# passlight.net
KiCad netlist of a schematic drawn in EAGLE
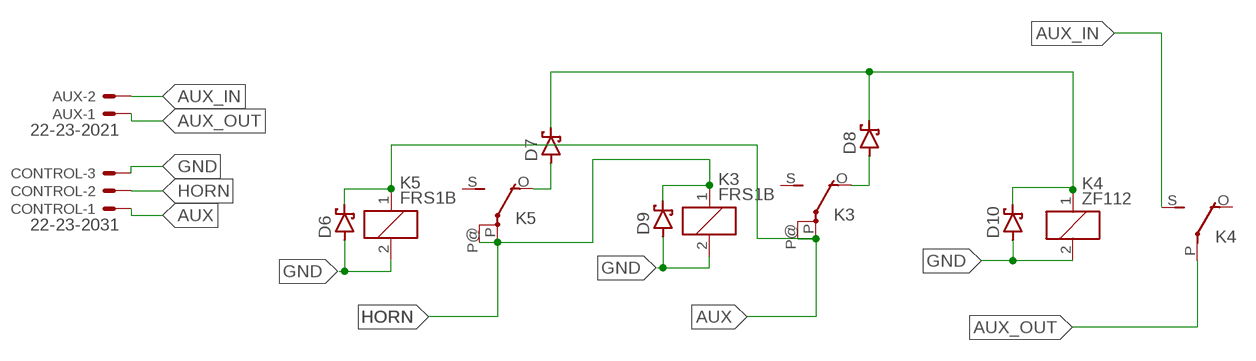
[diagram p0: schematic, sheet 1]

(export (version "E")
  (design (tool "Eeschema 10.0.6"))
  (components
    (comp (ref "AUX")
      (value "22-23-2021")
      (footprint "eagle-import:22-23-2021")
      (fields (field (name "MF") "MOLEX"))
      (libsource (lib "eagle-import") (part "22-23-2021"))
    )
    (comp (ref "CONTROL")
      (value "22-23-2031")
      (footprint "eagle-import:22-23-2031")
      (fields (field (name "MF") "MOLEX"))
      (libsource (lib "eagle-import") (part "22-23-2031"))
    )
    (comp (ref "D6")
      (value "SCHOTTKY-DIODESMD")
      (footprint "eagle-import:SMB")
      (libsource (lib "eagle-import") (part "SCHOTTKY-DIODESMD"))
    )
    (comp (ref "D7")
      (value "SCHOTTKY-DIODESMD")
      (footprint "eagle-import:SMB")
      (libsource (lib "eagle-import") (part "SCHOTTKY-DIODESMD"))
    )
    (comp (ref "D8")
      (value "SCHOTTKY-DIODESMD")
      (footprint "eagle-import:SMB")
      (libsource (lib "eagle-import") (part "SCHOTTKY-DIODESMD"))
    )
    (comp (ref "D9")
      (value "SCHOTTKY-DIODESMD")
      (footprint "eagle-import:SMB")
      (libsource (lib "eagle-import") (part "SCHOTTKY-DIODESMD"))
    )
    (comp (ref "D10")
      (value "SCHOTTKY-DIODESMD")
      (footprint "eagle-import:SMB")
      (libsource (lib "eagle-import") (part "SCHOTTKY-DIODESMD"))
    )
    (comp (ref "K3")
      (value "FRS1B")
      (footprint "eagle-import:FRS1B")
      (libsource (lib "eagle-import") (part "FRS1B"))
    )
    (comp (ref "K4")
      (value "ZF112")
      (footprint "eagle-import:ZF112")
      (libsource (lib "eagle-import") (part "ZF112"))
    )
    (comp (ref "K5")
      (value "FRS1B")
      (footprint "eagle-import:FRS1B")
      (libsource (lib "eagle-import") (part "FRS1B"))
    )
  )
  (nets
    (net (code "1") (name "AUX") (class "Default")
      (node (ref "CONTROL") (pin "1") (pinfunction "S_1") (pintype "passive"))
      (node (ref "D6") (pin "C") (pinfunction "C_C") (pintype "passive"))
      (node (ref "K3") (pin "P") (pinfunction "P_P") (pintype "passive"))
      (node (ref "K3") (pin "P@") (pinfunction "P_P@") (pintype "passive"))
      (node (ref "K5") (pin "1") (pinfunction "1_1") (pintype "passive"))
    )
    (net (code "2") (name "AUX_IN") (class "Default")
      (node (ref "AUX") (pin "2") (pinfunction "S_2") (pintype "passive"))
      (node (ref "K4") (pin "S") (pinfunction "S_S") (pintype "passive"))
    )
    (net (code "3") (name "AUX_OUT") (class "Default")
      (node (ref "AUX") (pin "1") (pinfunction "S_1") (pintype "passive"))
      (node (ref "K4") (pin "P") (pinfunction "P_P") (pintype "passive"))
    )
    (net (code "4") (name "GND") (class "Default")
      (node (ref "CONTROL") (pin "3") (pinfunction "S_3") (pintype "passive"))
      (node (ref "D10") (pin "A") (pinfunction "A_A") (pintype "passive"))
      (node (ref "D6") (pin "A") (pinfunction "A_A") (pintype "passive"))
      (node (ref "D9") (pin "A") (pinfunction "A_A") (pintype "passive"))
      (node (ref "K3") (pin "2") (pinfunction "2_2") (pintype "passive"))
      (node (ref "K4") (pin "2") (pinfunction "2_2") (pintype "passive"))
      (node (ref "K5") (pin "2") (pinfunction "2_2") (pintype "passive"))
    )
    (net (code "5") (name "HORN") (class "Default")
      (node (ref "CONTROL") (pin "2") (pinfunction "S_2") (pintype "passive"))
      (node (ref "D9") (pin "C") (pinfunction "C_C") (pintype "passive"))
      (node (ref "K3") (pin "1") (pinfunction "1_1") (pintype "passive"))
      (node (ref "K5") (pin "P") (pinfunction "P_P") (pintype "passive"))
      (node (ref "K5") (pin "P@") (pinfunction "P_P@") (pintype "passive"))
    )
    (net (code "6") (name "Net-(D7-PadA)") (class "Default")
      (node (ref "D7") (pin "A") (pinfunction "A_A") (pintype "passive"))
      (node (ref "K5") (pin "O") (pinfunction "O_O") (pintype "passive"))
    )
    (net (code "7") (name "Net-(D8-PadA)") (class "Default")
      (node (ref "D8") (pin "A") (pinfunction "A_A") (pintype "passive"))
      (node (ref "K3") (pin "O") (pinfunction "O_O") (pintype "passive"))
    )
    (net (code "8") (name "Net-(D10-PadC)") (class "Default")
      (node (ref "D10") (pin "C") (pinfunction "C_C") (pintype "passive"))
      (node (ref "D7") (pin "C") (pinfunction "C_C") (pintype "passive"))
      (node (ref "D8") (pin "C") (pinfunction "C_C") (pintype "passive"))
      (node (ref "K4") (pin "1") (pinfunction "1_1") (pintype "passive"))
    )
    (net (code "9") (name "unconnected-(K3-PadS)") (class "Default")
      (node (ref "K3") (pin "S") (pinfunction "S_S") (pintype "passive"))
    )
    (net (code "10") (name "unconnected-(K4-PadO)") (class "Default")
      (node (ref "K4") (pin "O") (pinfunction "O_O") (pintype "passive"))
    )
    (net (code "11") (name "unconnected-(K5-PadS)") (class "Default")
      (node (ref "K5") (pin "S") (pinfunction "S_S") (pintype "passive"))
    )
  )
)
